# MCED_IO.net
KiCad netlist of a schematic drawn in Altium Designer
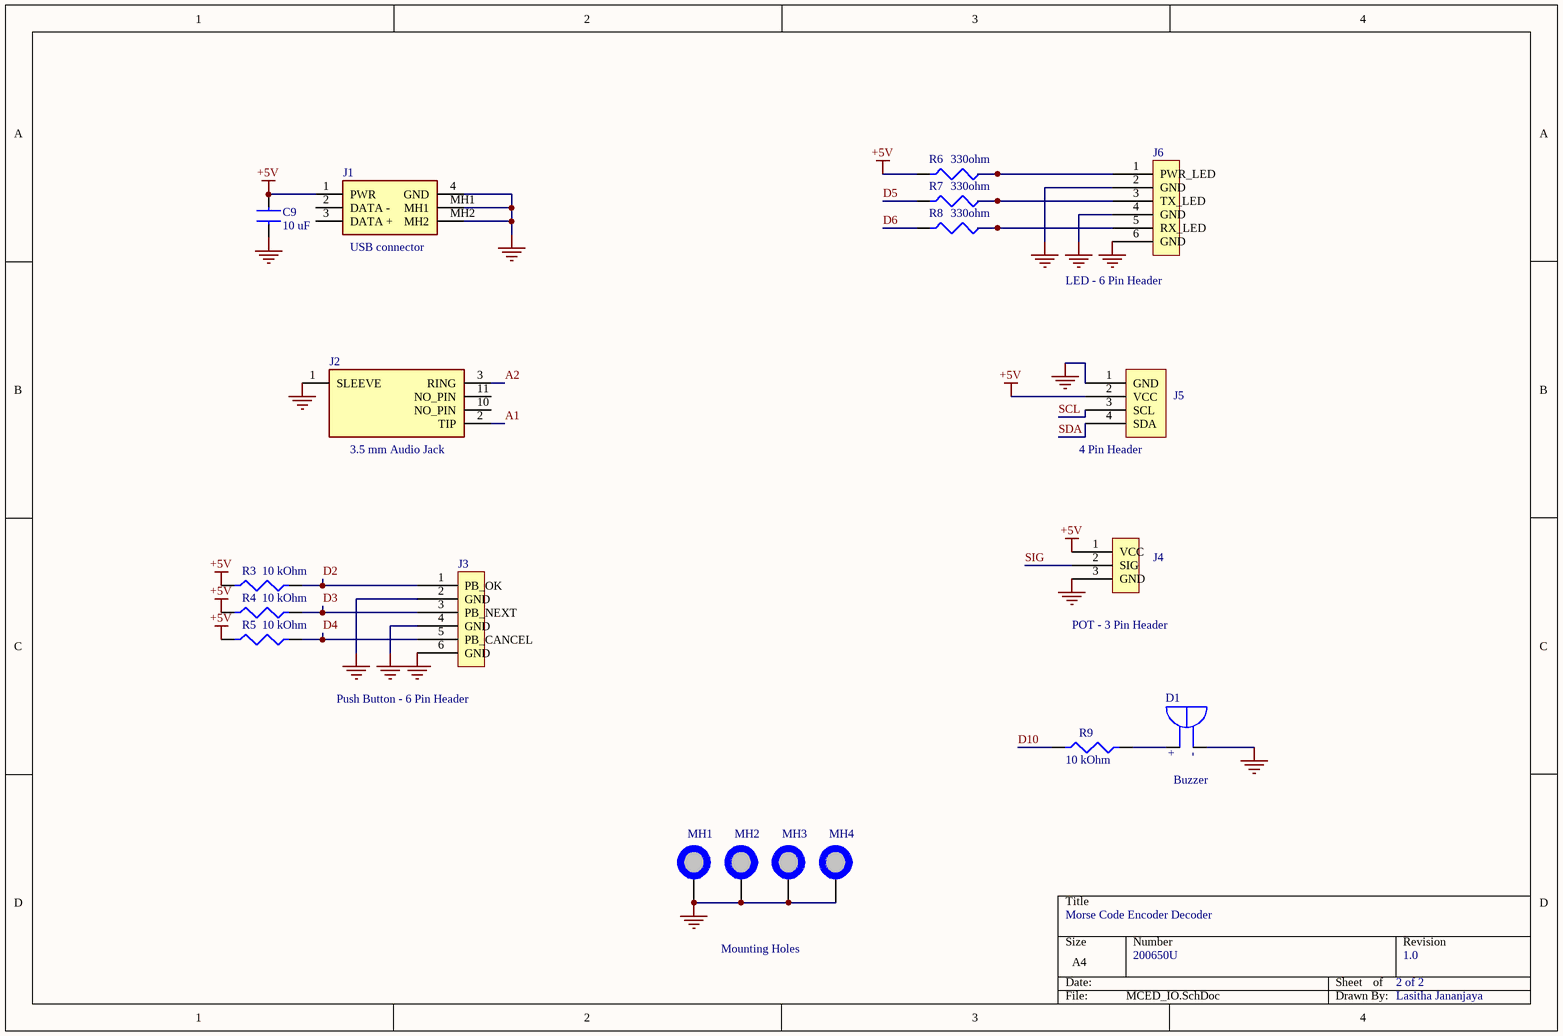
[diagram p0: MCED_IO.SchDoc]

(export (version "E")
  (design (tool "Eeschema 10.0.6"))
  (components
    (comp (ref "C9")
      (value "10 uF")
      (footprint "C0805")
      (fields
        (field (name "MANUFACTURER") "Samsung")
        (field (name "MANUFACTURER PART NUMBER") "CL21A106KBYQNNE")
      )
      (libsource (lib "MCED_Schlib") (part "CL21A106KBYQNNE"))
    )
    (comp (ref "D1")
      (value "Buzzer")
      (footprint "Buzzer")
      (fields (field (name "MF") "Kingstate") (field (name "MP") "KXG1201C"))
      (libsource (lib "MCED_Schlib") (part "KXG1201C"))
    )
    (comp (ref "J1")
      (value "USB connector")
      (footprint "USB 2.0 type B 617291011BLF")
      (description "USB 2.0 connector, Type B, Receptacle, Through Hole, 30u GXT Contact, 4 Pins, 1.57mm PCB")
      (fields
        (field (name "MANUFACTURER") "Amphenol ICC / FCI")
        (field (name "MANUFACTURER PART NUMBER") "61729-1011BLF")
      )
      (libsource (lib "MCED_Schlib") (part "61729-1011BLF"))
    )
    (comp (ref "J2")
      (value "3.5 mm Audio Jack")
      (footprint "Audio Jack SJ13523N")
      (description "3.5 mm Audio Jack, Female, 3 Pole(s), Solder Terminal, Jack")
      (fields
        (field (name "MANUFACTURER") "CUI Devices")
        (field (name "MANUFACTURER PART NUMBER") "SJ1-3523N")
      )
      (libsource (lib "MCED_Schlib") (part "SJ1-3523N"))
    )
    (comp (ref "J3")
      (value "Push Button - 6 Pin Header")
      (footprint "6 PIN HEADER")
      (description "6 Pin Header Board Connector")
      (fields (field (name "MANUFACTURER") "3M") (field (name "MANUFACTURER PART NUMBER") "929850-01-06-RB"))
      (libsource (lib "MCED_Schlib") (part "929850-01-06-RB"))
    )
    (comp (ref "J4")
      (value "POT - 3 Pin Header")
      (footprint "3 PIN HEADER")
      (description "3 Pin Header Board Connector, 3 Contact(s), 1 Row(s), Female, Straight, Solder Terminal, Socket")
      (fields (field (name "MANUFACTURER") "3M") (field (name "MANUFACTURER PART NUMBER") "929850-01-03-RA"))
      (libsource (lib "MCED_Schlib") (part "929850-01-03-RA"))
    )
    (comp (ref "J5")
      (value "4 Pin Header")
      (footprint "4 Pin Header")
      (fields (field (name "MANUFACTURER") "Harwin") (field (name "MANUFACTURER PART NUMBER") "M20-7820446"))
      (libsource (lib "MCED_Schlib") (part "M20-7820446"))
    )
    (comp (ref "J6")
      (value "LED - 6 Pin Header")
      (footprint "6 PIN HEADER")
      (description "6 Pin Header Board Connector")
      (fields (field (name "MANUFACTURER") "3M") (field (name "MANUFACTURER PART NUMBER") "929850-01-06-RB"))
      (libsource (lib "MCED_Schlib") (part "929850-01-06-RB"))
    )
    (comp (ref "MH1")
      (value "MH")
      (footprint "Mounting Hole")
      (libsource (lib "MCED_Schlib") (part "Mounting Hole"))
    )
    (comp (ref "MH2")
      (value "MH")
      (footprint "Mounting Hole")
      (libsource (lib "MCED_Schlib") (part "Mounting Hole"))
    )
    (comp (ref "MH3")
      (value "MH")
      (footprint "Mounting Hole")
      (libsource (lib "MCED_Schlib") (part "Mounting Hole"))
    )
    (comp (ref "MH4")
      (value "MH")
      (footprint "Mounting Hole")
      (libsource (lib "MCED_Schlib") (part "Mounting Hole"))
    )
    (comp (ref "R3")
      (value "10 kOhm")
      (footprint "10K")
      (description "10 kOhm, Fixed Resistor, Thin Film, 0.2W, 10000ohm, 150V, 0.5% +/-Tol, -25,25ppm/Cel, 0805")
      (fields
        (field (name "MANUFACTURER") "Vishay Beyschlag")
        (field (name "MANUFACTURER PART NUMBER") "MCU0805MD1002DP500")
      )
      (libsource (lib "MCED_Schlib") (part "MCU0805MD1002DP500"))
    )
    (comp (ref "R4")
      (value "10 kOhm")
      (footprint "10K")
      (description "10 kOhm, Fixed Resistor, Thin Film, 0.2W, 10000ohm, 150V, 0.5% +/-Tol, -25,25ppm/Cel, 0805")
      (fields
        (field (name "MANUFACTURER") "Vishay Beyschlag")
        (field (name "MANUFACTURER PART NUMBER") "MCU0805MD1002DP500")
      )
      (libsource (lib "MCED_Schlib") (part "MCU0805MD1002DP500"))
    )
    (comp (ref "R5")
      (value "10 kOhm")
      (footprint "10K")
      (description "10 kOhm, Fixed Resistor, Thin Film, 0.2W, 10000ohm, 150V, 0.5% +/-Tol, -25,25ppm/Cel, 0805")
      (fields
        (field (name "MANUFACTURER") "Vishay Beyschlag")
        (field (name "MANUFACTURER PART NUMBER") "MCU0805MD1002DP500")
      )
      (libsource (lib "MCED_Schlib") (part "MCU0805MD1002DP500"))
    )
    (comp (ref "R6")
      (value "330ohm")
      (footprint "300Ohm RESC2012X60N")
      (fields
        (field (name "MANUFACTURER") "Vishay")
        (field (name "MANUFACTURER PART NUMBER") "CRCW0805330RFKEA")
        (field (name "TOLERANCE") "1%")
      )
      (libsource (lib "MCED_Schlib") (part "CRCW0805330RFKEA"))
    )
    (comp (ref "R7")
      (value "330ohm")
      (footprint "300Ohm RESC2012X60N")
      (fields
        (field (name "MANUFACTURER") "Vishay")
        (field (name "MANUFACTURER PART NUMBER") "CRCW0805330RFKEA")
        (field (name "TOLERANCE") "1%")
      )
      (libsource (lib "MCED_Schlib") (part "CRCW0805330RFKEA"))
    )
    (comp (ref "R8")
      (value "330ohm")
      (footprint "300Ohm RESC2012X60N")
      (fields
        (field (name "MANUFACTURER") "Vishay")
        (field (name "MANUFACTURER PART NUMBER") "CRCW0805330RFKEA")
        (field (name "TOLERANCE") "1%")
      )
      (libsource (lib "MCED_Schlib") (part "CRCW0805330RFKEA"))
    )
    (comp (ref "R9")
      (value "10 kOhm")
      (footprint "10K")
      (description "10 kOhm, Fixed Resistor, Thin Film, 0.2W, 10000ohm, 150V, 0.5% +/-Tol, -25,25ppm/Cel, 0805")
      (fields
        (field (name "MANUFACTURER") "Vishay Beyschlag")
        (field (name "MANUFACTURER PART NUMBER") "MCU0805MD1002DP500")
      )
      (libsource (lib "MCED_Schlib") (part "MCU0805MD1002DP500"))
    )
  )
  (nets
    (net (code "1") (name "+5V") (class "Default")
      (node (ref "C9") (pin "2") (pinfunction "2_2") (pintype "passive"))
      (node (ref "J1") (pin "1") (pinfunction "PWR_1") (pintype "passive"))
      (node (ref "J4") (pin "1") (pinfunction "VCC_1") (pintype "passive"))
      (node (ref "J5") (pin "2") (pinfunction "VCC_2") (pintype "passive"))
      (node (ref "R3") (pin "2") (pinfunction "2_2") (pintype "passive"))
      (node (ref "R4") (pin "2") (pinfunction "2_2") (pintype "passive"))
      (node (ref "R5") (pin "2") (pinfunction "2_2") (pintype "passive"))
      (node (ref "R6") (pin "1") (pinfunction "1_1") (pintype "passive"))
    )
    (net (code "2") (name "/A1") (class "Default")
      (node (ref "J2") (pin "2") (pinfunction "TIP_2") (pintype "passive"))
    )
    (net (code "3") (name "/A2") (class "Default")
      (node (ref "J2") (pin "3") (pinfunction "RING_3") (pintype "passive"))
    )
    (net (code "4") (name "/D2") (class "Default")
      (node (ref "J3") (pin "1") (pinfunction "PB_OK_1") (pintype "passive"))
      (node (ref "R3") (pin "1") (pinfunction "1_1") (pintype "passive"))
    )
    (net (code "5") (name "/D3") (class "Default")
      (node (ref "J3") (pin "3") (pinfunction "PB_NEXT_3") (pintype "passive"))
      (node (ref "R4") (pin "1") (pinfunction "1_1") (pintype "passive"))
    )
    (net (code "6") (name "/D4") (class "Default")
      (node (ref "J3") (pin "5") (pinfunction "PB_CANCEL_5") (pintype "passive"))
      (node (ref "R5") (pin "1") (pinfunction "1_1") (pintype "passive"))
    )
    (net (code "7") (name "/D5") (class "Default")
      (node (ref "R7") (pin "1") (pinfunction "1_1") (pintype "passive"))
    )
    (net (code "8") (name "/D6") (class "Default")
      (node (ref "R8") (pin "1") (pinfunction "1_1") (pintype "passive"))
    )
    (net (code "9") (name "/D10") (class "Default")
      (node (ref "R9") (pin "2") (pinfunction "2_2") (pintype "passive"))
    )
    (net (code "10") (name "/SCL") (class "Default")
      (node (ref "J5") (pin "3") (pinfunction "SCL_3") (pintype "passive"))
    )
    (net (code "11") (name "/SDA") (class "Default")
      (node (ref "J5") (pin "4") (pinfunction "SDA_4") (pintype "passive"))
    )
    (net (code "12") (name "/SIG") (class "Default")
      (node (ref "J4") (pin "2") (pinfunction "SIG_2") (pintype "passive"))
    )
    (net (code "13") (name "GND") (class "Default")
      (node (ref "C9") (pin "1") (pinfunction "1_1") (pintype "passive"))
      (node (ref "D1") (pin "N") (pinfunction "NEG_N") (pintype "passive"))
      (node (ref "J1") (pin "4") (pinfunction "GND_4") (pintype "passive"))
      (node (ref "J1") (pin "MH1") (pinfunction "MH1_MH1") (pintype "passive"))
      (node (ref "J1") (pin "MH2") (pinfunction "MH2_MH2") (pintype "passive"))
      (node (ref "J2") (pin "1") (pinfunction "SLEEVE_1") (pintype "passive"))
      (node (ref "J3") (pin "2") (pinfunction "GND_2") (pintype "passive"))
      (node (ref "J3") (pin "4") (pinfunction "GND_4") (pintype "passive"))
      (node (ref "J3") (pin "6") (pinfunction "GND_6") (pintype "passive"))
      (node (ref "J4") (pin "3") (pinfunction "GND_3") (pintype "passive"))
      (node (ref "J5") (pin "1") (pinfunction "GND_1") (pintype "passive"))
      (node (ref "J6") (pin "2") (pinfunction "GND_2") (pintype "passive"))
      (node (ref "J6") (pin "4") (pinfunction "GND_4") (pintype "passive"))
      (node (ref "J6") (pin "6") (pinfunction "GND_6") (pintype "passive"))
      (node (ref "MH1") (pin "1") (pinfunction "1_1") (pintype "passive"))
      (node (ref "MH2") (pin "1") (pinfunction "1_1") (pintype "passive"))
      (node (ref "MH3") (pin "1") (pinfunction "1_1") (pintype "passive"))
      (node (ref "MH4") (pin "1") (pinfunction "1_1") (pintype "passive"))
    )
    (net (code "14") (name "Net-(D1-POS)") (class "Default")
      (node (ref "D1") (pin "P") (pinfunction "POS_P") (pintype "passive"))
      (node (ref "R9") (pin "1") (pinfunction "1_1") (pintype "passive"))
    )
    (net (code "15") (name "Net-(J6-PB_CANCEL)") (class "Default")
      (node (ref "J6") (pin "5") (pinfunction "PB_CANCEL_5") (pintype "passive"))
      (node (ref "R8") (pin "2") (pinfunction "2_2") (pintype "passive"))
    )
    (net (code "16") (name "Net-(J6-PB_NEXT)") (class "Default")
      (node (ref "J6") (pin "3") (pinfunction "PB_NEXT_3") (pintype "passive"))
      (node (ref "R7") (pin "2") (pinfunction "2_2") (pintype "passive"))
    )
    (net (code "17") (name "Net-(J6-PB_OK)") (class "Default")
      (node (ref "J6") (pin "1") (pinfunction "PB_OK_1") (pintype "passive"))
      (node (ref "R6") (pin "2") (pinfunction "2_2") (pintype "passive"))
    )
    (net (code "18") (name "unconnected-(J1-DATA_+-Pad3)") (class "Default")
      (node (ref "J1") (pin "3") (pinfunction "DATA_+_3") (pintype "passive"))
    )
    (net (code "19") (name "unconnected-(J1-DATA_--Pad2)") (class "Default")
      (node (ref "J1") (pin "2") (pinfunction "DATA_-_2") (pintype "passive"))
    )
    (net (code "20") (name "unconnected-(J2-NO_PIN-Pad10)") (class "Default")
      (node (ref "J2") (pin "10") (pinfunction "NO_PIN_10") (pintype "passive"))
    )
    (net (code "21") (name "unconnected-(J2-NO_PIN-Pad11)") (class "Default")
      (node (ref "J2") (pin "11") (pinfunction "NO_PIN_11") (pintype "passive"))
    )
  )
)
